# Sheet1.net
KiCad netlist of a schematic drawn in Altium Designer
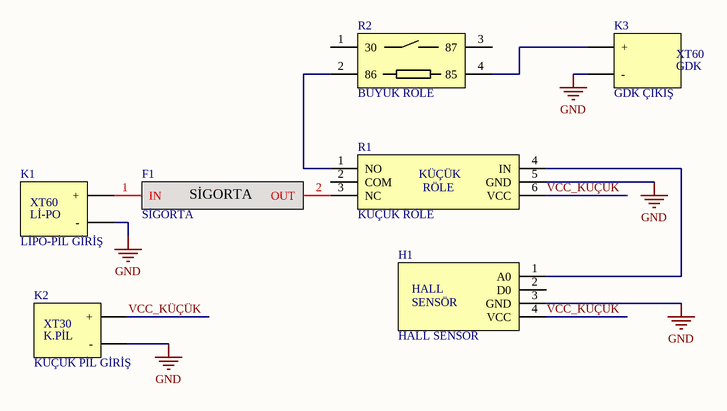
[diagram p0: Sheet1.SchDoc]

(export (version "E")
  (design (tool "Eeschema 10.0.6"))
  (components
    (comp (ref "F1") (value "SİGORTA") (libsource (lib "Schlib2") (part "SİGORTA")))
    (comp (ref "H1")
      (value "HALL SENSÖR")
      (footprint "HALL SENSÖR")
      (libsource (lib "Schlib1") (part "HALL SENSÖR"))
    )
    (comp (ref "K1")
      (value "LİPO-PİL GİRİŞ")
      (footprint "LİPO-PİL GİRİŞ")
      (libsource (lib "Schlib1") (part "LİPO-PİL GİRİŞ"))
    )
    (comp (ref "K2")
      (value "KÜÇÜK PİL GİRİŞ")
      (footprint "KÜÇÜK PİL GİRİŞ")
      (libsource (lib "Schlib1") (part "KÜÇÜK PİL GİRİŞ"))
    )
    (comp (ref "K3")
      (value "GDK ÇIKIŞ")
      (footprint "GDK ÇIKIŞ")
      (libsource (lib "Schlib1") (part "GDK ÇIKIŞ"))
    )
    (comp (ref "R1")
      (value "KÜÇÜK RÖLE")
      (footprint "KÜÇÜK RÖLE")
      (libsource (lib "Schlib1") (part "KÜÇÜK RÖLE"))
    )
    (comp (ref "R2")
      (value "BÜYÜK RÖLE")
      (footprint "BÜYÜK RÖLE")
      (libsource (lib "Schlib1") (part "BÜYÜK RÖLE"))
    )
  )
  (nets
    (net (code "1") (name "/VCC_KÜÇÜK") (class "Default")
      (node (ref "H1") (pin "4") (pinfunction "VCC_4") (pintype "passive"))
      (node (ref "K2") (pin "P") (pinfunction "+_P") (pintype "passive"))
      (node (ref "R1") (pin "6") (pinfunction "VCC_6") (pintype "passive"))
    )
    (net (code "2") (name "GND") (class "Default")
      (node (ref "H1") (pin "3") (pinfunction "GND_3") (pintype "passive"))
      (node (ref "K1") (pin "2") (pinfunction "-_2") (pintype "passive"))
      (node (ref "K2") (pin "N") (pinfunction "-_N") (pintype "passive"))
      (node (ref "K3") (pin "2") (pinfunction "-_2") (pintype "passive"))
      (node (ref "R1") (pin "5") (pinfunction "GND_5") (pintype "passive"))
    )
    (net (code "3") (name "Net-(F1-IN)") (class "Default")
      (node (ref "F1") (pin "1") (pinfunction "IN_1") (pintype "passive"))
      (node (ref "K1") (pin "1") (pinfunction "+_1") (pintype "passive"))
    )
    (net (code "4") (name "Net-(F1-OUT)") (class "Default")
      (node (ref "F1") (pin "2") (pinfunction "OUT_2") (pintype "passive"))
      (node (ref "R1") (pin "3") (pinfunction "NC_3") (pintype "passive"))
    )
    (net (code "5") (name "Net-(H1-A0)") (class "Default")
      (node (ref "H1") (pin "1") (pinfunction "A0_1") (pintype "passive"))
      (node (ref "R1") (pin "4") (pinfunction "IN_4") (pintype "passive"))
    )
    (net (code "6") (name "Net-(K3-+)") (class "Default")
      (node (ref "K3") (pin "1") (pinfunction "+_1") (pintype "passive"))
      (node (ref "R2") (pin "4") (pinfunction "85_4") (pintype "passive"))
    )
    (net (code "7") (name "Net-(R1-NO)") (class "Default")
      (node (ref "R1") (pin "1") (pinfunction "NO_1") (pintype "passive"))
      (node (ref "R2") (pin "2") (pinfunction "86_2") (pintype "passive"))
    )
    (net (code "8") (name "unconnected-(H1-D0-Pad2)") (class "Default")
      (node (ref "H1") (pin "2") (pinfunction "D0_2") (pintype "passive"))
    )
    (net (code "9") (name "unconnected-(R1-COM-Pad2)") (class "Default")
      (node (ref "R1") (pin "2") (pinfunction "COM_2") (pintype "passive"))
    )
    (net (code "10") (name "unconnected-(R2-30-Pad1)") (class "Default")
      (node (ref "R2") (pin "1") (pinfunction "30_1") (pintype "passive"))
    )
    (net (code "11") (name "unconnected-(R2-87-Pad3)") (class "Default")
      (node (ref "R2") (pin "3") (pinfunction "87_3") (pintype "passive"))
    )
  )
)
